# waveshare_v4.net
KiCad netlist of a schematic drawn in EAGLE
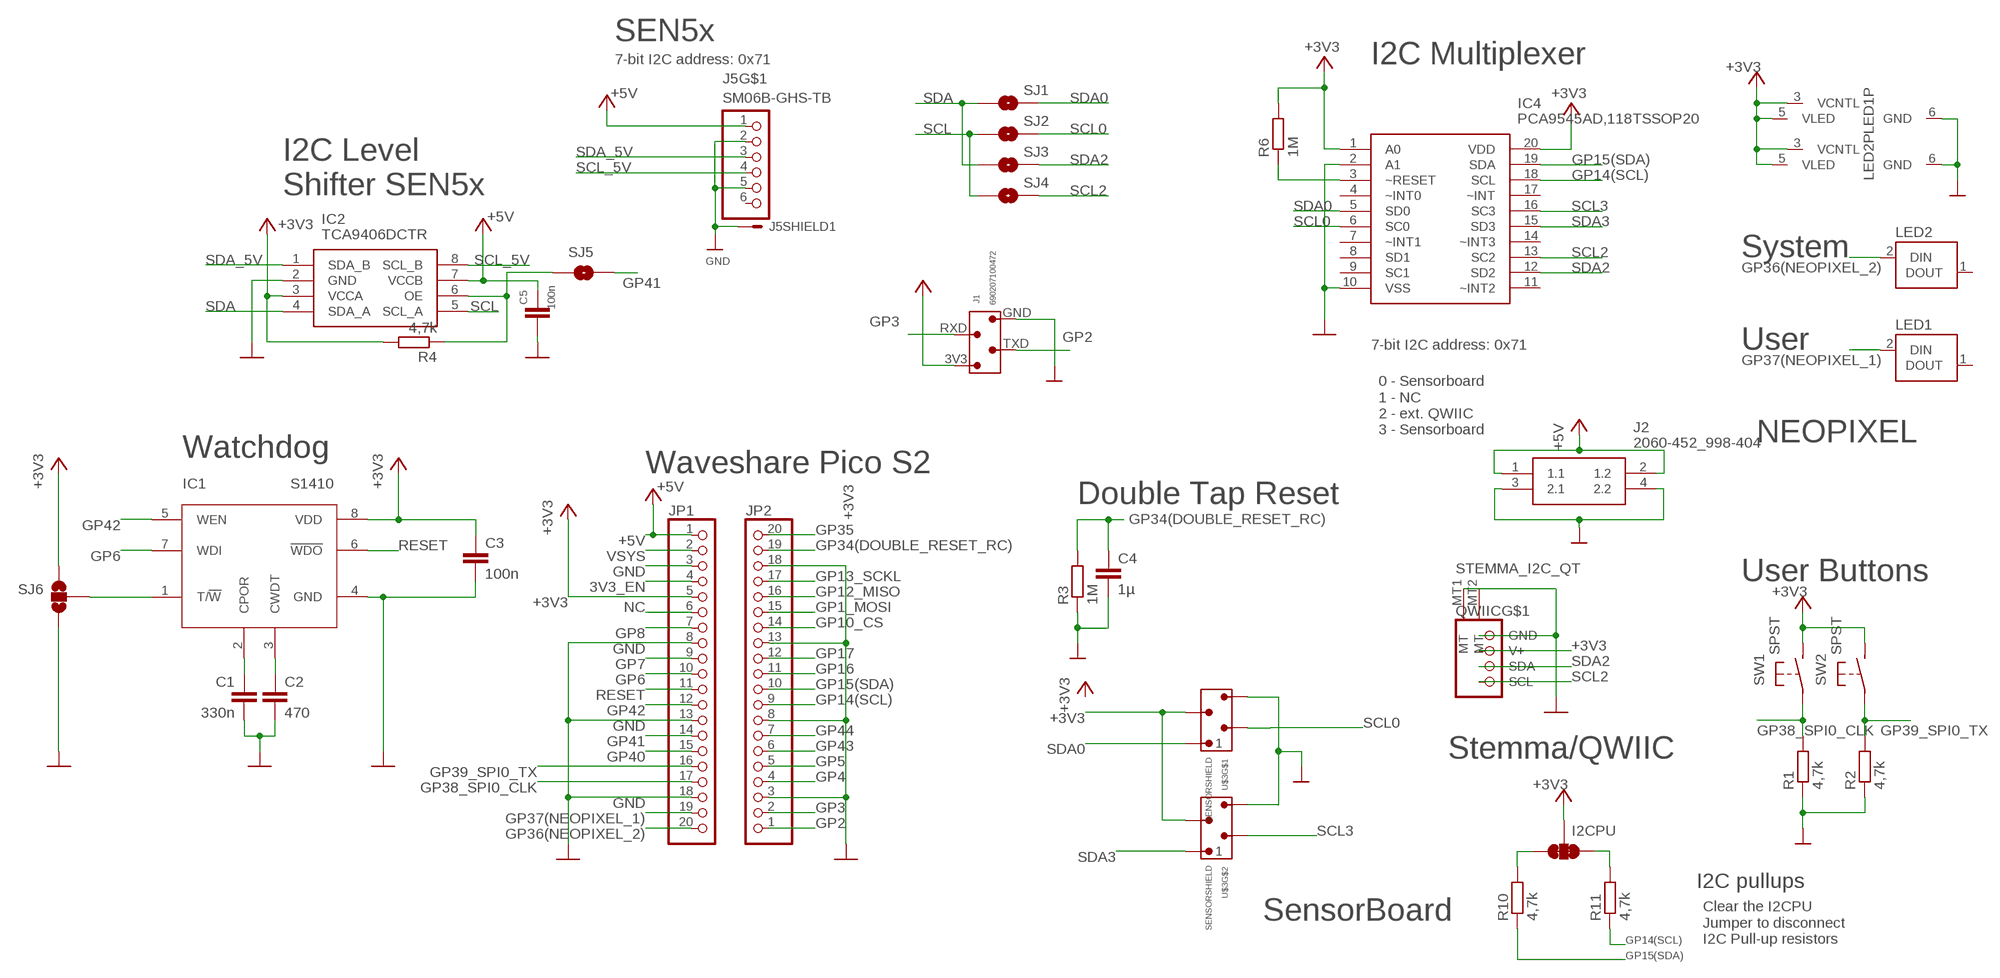
[diagram p0: schematic, sheet 1]

(export (version "E")
  (design (tool "Eeschema 10.0.6"))
  (components
    (comp (ref "C1")
      (value "330n")
      (footprint "eagle-import:C0603")
      (libsource (lib "eagle-import") (part "C-EUC0603"))
    )
    (comp (ref "C2")
      (value "470")
      (footprint "eagle-import:C0603")
      (libsource (lib "eagle-import") (part "C-EUC0603"))
    )
    (comp (ref "C3")
      (value "100n")
      (footprint "eagle-import:C0603")
      (libsource (lib "eagle-import") (part "C-EUC0603"))
    )
    (comp (ref "C4")
      (value "1µ")
      (footprint "eagle-import:C0603")
      (libsource (lib "eagle-import") (part "C-EUC0603"))
    )
    (comp (ref "C5")
      (value "100n")
      (footprint "eagle-import:C0603")
      (libsource (lib "eagle-import") (part "C-EUC0603"))
    )
    (comp (ref "I2CPU")
      (value "I2C PU")
      (footprint "eagle-import:SMT-JUMPER_3_2-NC_TRACE_SILK")
      (libsource (lib "eagle-import") (part "JUMPER-SMT_3_2-NC_TRACE_SILK"))
    )
    (comp (ref "IC1")
      (value "S1410")
      (footprint "eagle-import:MSOP08")
      (libsource (lib "eagle-import") (part "S1410"))
    )
    (comp (ref "IC2")
      (value "TCA9406DCTR")
      (footprint "eagle-import:SOP65P400X130-8N")
      (fields (field (name "MOUSER_PART_NUMBER") "595-TCA9406DCTR"))
      (libsource (lib "eagle-import") (part "TCA9406DCTR"))
    )
    (comp (ref "IC4")
      (value "PCA9545AD,118TSSOP20")
      (footprint "eagle-import:TSSOP20")
      (libsource (lib "eagle-import") (part "PCA9545AD,118TSSOP20"))
    )
    (comp (ref "J1")
      (value "690207100472")
      (footprint "eagle-import:LORASHIELD")
      (libsource (lib "eagle-import") (part "LORASHIELD"))
    )
    (comp (ref "J2")
      (value "2060-452_998-404")
      (footprint "eagle-import:2060452998404")
      (fields (field (name "ARROW_PART_NUMBER") "2060-452/998-404"))
      (libsource (lib "eagle-import") (part "2060-452_998-404"))
    )
    (comp (ref "J5")
      (value "SM06B-GHS-TB")
      (footprint "eagle-import:JST-PH-06-SMD")
      (libsource (lib "eagle-import") (part "JST-PH-06-SMDSMD"))
    )
    (comp (ref "JP1")
      (value "PINHD-1X20")
      (footprint "eagle-import:1X20")
      (libsource (lib "eagle-import") (part "PINHD-1X20"))
    )
    (comp (ref "JP2")
      (value "PINHD-1X20")
      (footprint "eagle-import:1X20")
      (libsource (lib "eagle-import") (part "PINHD-1X20"))
    )
    (comp (ref "LED1")
      (value "WS2812WS2812")
      (footprint "eagle-import:WS2812")
      (libsource (lib "eagle-import") (part "WS2812WS2812"))
    )
    (comp (ref "LED2")
      (value "WS2812WS2812")
      (footprint "eagle-import:WS2812")
      (libsource (lib "eagle-import") (part "WS2812WS2812"))
    )
    (comp (ref "QWIIC")
      (value "STEMMA_I2C_QT")
      (footprint "eagle-import:JST_SH4")
      (libsource (lib "eagle-import") (part "STEMMA_I2C_QT"))
    )
    (comp (ref "R1")
      (value "4,7k")
      (footprint "eagle-import:R0603")
      (libsource (lib "eagle-import") (part "R-EU_R0603"))
    )
    (comp (ref "R2")
      (value "4,7k")
      (footprint "eagle-import:R0603")
      (libsource (lib "eagle-import") (part "R-EU_R0603"))
    )
    (comp (ref "R3")
      (value "1M")
      (footprint "eagle-import:R0603")
      (libsource (lib "eagle-import") (part "R-EU_R0603"))
    )
    (comp (ref "R4")
      (value "4,7k")
      (footprint "eagle-import:R0603")
      (libsource (lib "eagle-import") (part "R-EU_R0603"))
    )
    (comp (ref "R6")
      (value "1M")
      (footprint "eagle-import:R0603")
      (libsource (lib "eagle-import") (part "R-EU_R0603"))
    )
    (comp (ref "R10")
      (value "4,7k")
      (footprint "eagle-import:R0603")
      (libsource (lib "eagle-import") (part "R-EU_R0603"))
    )
    (comp (ref "R11")
      (value "4,7k")
      (footprint "eagle-import:R0603")
      (libsource (lib "eagle-import") (part "R-EU_R0603"))
    )
    (comp (ref "SJ1")
      (value "SOLDERJUMPERNO")
      (footprint "eagle-import:SJ_2S-NO")
      (libsource (lib "eagle-import") (part "SOLDERJUMPERNO"))
    )
    (comp (ref "SJ2")
      (value "SOLDERJUMPERNO")
      (footprint "eagle-import:SJ_2S-NO")
      (libsource (lib "eagle-import") (part "SOLDERJUMPERNO"))
    )
    (comp (ref "SJ3")
      (value "SOLDERJUMPERNO")
      (footprint "eagle-import:SJ_2S-NO")
      (libsource (lib "eagle-import") (part "SOLDERJUMPERNO"))
    )
    (comp (ref "SJ4")
      (value "SOLDERJUMPERNO")
      (footprint "eagle-import:SJ_2S-NO")
      (libsource (lib "eagle-import") (part "SOLDERJUMPERNO"))
    )
    (comp (ref "SJ5")
      (value "SOLDERJUMPERNO")
      (footprint "eagle-import:SJ_2S-NO")
      (libsource (lib "eagle-import") (part "SOLDERJUMPERNO"))
    )
    (comp (ref "SJ6")
      (value "SOLDERJUMPER_2WAYTRACE1&2")
      (footprint "eagle-import:SJ_3_TRACE1&2")
      (libsource (lib "eagle-import") (part "SOLDERJUMPER_2WAYTRACE1&2"))
    )
    (comp (ref "SW1")
      (value "SPST")
      (footprint "eagle-import:DTSM-32S-B")
      (libsource (lib "eagle-import") (part "SPST"))
    )
    (comp (ref "SW2")
      (value "SPST")
      (footprint "eagle-import:DTSM-32S-B")
      (libsource (lib "eagle-import") (part "SPST"))
    )
    (comp (ref "U$3")
      (value "SENSORSHIELD")
      (footprint "eagle-import:SENSORSHIELD")
      (libsource (lib "eagle-import") (part "SENSORSHIELD"))
    )
  )
  (nets
    (net (code "1") (name "+3V3") (class "Default")
      (node (ref "C3") (pin "1") (pinfunction "1_1") (pintype "passive"))
      (node (ref "I2CPU") (pin "2") (pinfunction "2_2") (pintype "passive"))
      (node (ref "IC1") (pin "8") (pinfunction "VDD_8") (pintype "bidirectional"))
      (node (ref "IC2") (pin "3") (pinfunction "VCCA_3") (pintype "bidirectional"))
      (node (ref "IC4") (pin "1") (pinfunction "A0_1") (pintype "bidirectional"))
      (node (ref "IC4") (pin "20") (pinfunction "VDD_20") (pintype "bidirectional"))
      (node (ref "J1") (pin "3V3") (pinfunction "4_3V3") (pintype "passive"))
      (node (ref "JP1") (pin "5") (pinfunction "5_5") (pintype "passive"))
      (node (ref "LED1") (pin "3") (pinfunction "VCNTL_3") (pintype "power_in"))
      (node (ref "LED1") (pin "5") (pinfunction "VLED_5") (pintype "power_in"))
      (node (ref "LED2") (pin "3") (pinfunction "VCNTL_3") (pintype "power_in"))
      (node (ref "LED2") (pin "5") (pinfunction "VLED_5") (pintype "power_in"))
      (node (ref "QWIIC") (pin "2") (pinfunction "V+_2") (pintype "passive"))
      (node (ref "R4") (pin "2") (pinfunction "2_2") (pintype "passive"))
      (node (ref "R6") (pin "2") (pinfunction "2_2") (pintype "passive"))
      (node (ref "SJ6") (pin "1") (pinfunction "1_1") (pintype "passive"))
      (node (ref "SW1") (pin "P$2") (pinfunction "S_P$2") (pintype "passive"))
      (node (ref "SW2") (pin "P$2") (pinfunction "S_P$2") (pintype "passive"))
      (node (ref "U$3") (pin "3V3_1") (pinfunction "3_3V3_1") (pintype "passive"))
      (node (ref "U$3") (pin "3V3_2") (pinfunction "3_3V3_2") (pintype "passive"))
    )
    (net (code "2") (name "+5V") (class "Default")
      (node (ref "C5") (pin "1") (pinfunction "1_1") (pintype "passive"))
      (node (ref "IC2") (pin "7") (pinfunction "VCCB_7") (pintype "bidirectional"))
      (node (ref "J2") (pin "1") (pinfunction "1.1_1") (pintype "bidirectional"))
      (node (ref "J2") (pin "2") (pinfunction "1.2_2") (pintype "bidirectional"))
      (node (ref "J5") (pin "1") (pinfunction "1_1") (pintype "passive"))
      (node (ref "JP1") (pin "1") (pinfunction "1_1") (pintype "passive"))
    )
    (net (code "3") (name "/NC") (class "Default")
      (node (ref "JP1") (pin "6") (pinfunction "6_6") (pintype "passive"))
    )
    (net (code "4") (name "/SCL") (class "Default")
      (node (ref "IC2") (pin "5") (pinfunction "SCL_A_5") (pintype "bidirectional"))
      (node (ref "SJ2") (pin "1") (pinfunction "1_1") (pintype "passive"))
      (node (ref "SJ4") (pin "1") (pinfunction "1_1") (pintype "passive"))
    )
    (net (code "5") (name "/SCL_5V") (class "Default")
      (node (ref "IC2") (pin "8") (pinfunction "SCL_B_8") (pintype "bidirectional"))
      (node (ref "J5") (pin "4") (pinfunction "4_4") (pintype "passive"))
    )
    (net (code "6") (name "/SDA") (class "Default")
      (node (ref "IC2") (pin "4") (pinfunction "SDA_A_4") (pintype "bidirectional"))
      (node (ref "SJ1") (pin "1") (pinfunction "1_1") (pintype "passive"))
      (node (ref "SJ3") (pin "1") (pinfunction "1_1") (pintype "passive"))
    )
    (net (code "7") (name "/SDA_5V") (class "Default")
      (node (ref "IC2") (pin "1") (pinfunction "SDA_B_1") (pintype "bidirectional"))
      (node (ref "J5") (pin "3") (pinfunction "3_3") (pintype "passive"))
    )
    (net (code "8") (name "3V3_EN") (class "Default")
      (node (ref "JP1") (pin "4") (pinfunction "4_4") (pintype "passive"))
    )
    (net (code "9") (name "GND") (class "Default")
      (node (ref "C1") (pin "2") (pinfunction "2_2") (pintype "passive"))
      (node (ref "C2") (pin "2") (pinfunction "2_2") (pintype "passive"))
      (node (ref "C3") (pin "2") (pinfunction "2_2") (pintype "passive"))
      (node (ref "C4") (pin "2") (pinfunction "2_2") (pintype "passive"))
      (node (ref "C5") (pin "2") (pinfunction "2_2") (pintype "passive"))
      (node (ref "IC1") (pin "4") (pinfunction "GND_4") (pintype "bidirectional"))
      (node (ref "IC2") (pin "2") (pinfunction "GND_2") (pintype "bidirectional"))
      (node (ref "IC4") (pin "10") (pinfunction "VSS_10") (pintype "bidirectional"))
      (node (ref "IC4") (pin "2") (pinfunction "A1_2") (pintype "bidirectional"))
      (node (ref "J1") (pin "GND") (pinfunction "1_GND") (pintype "passive"))
      (node (ref "J2") (pin "3") (pinfunction "2.1_3") (pintype "bidirectional"))
      (node (ref "J2") (pin "4") (pinfunction "2.2_4") (pintype "bidirectional"))
      (node (ref "J5") (pin "2") (pinfunction "2_2") (pintype "passive"))
      (node (ref "J5") (pin "5") (pinfunction "5_5") (pintype "passive"))
      (node (ref "J5") (pin "7") (pinfunction "S_7") (pintype "passive"))
      (node (ref "J5") (pin "8") (pinfunction "S_8") (pintype "passive"))
      (node (ref "JP1") (pin "13") (pinfunction "13_13") (pintype "passive"))
      (node (ref "JP1") (pin "18") (pinfunction "18_18") (pintype "passive"))
      (node (ref "JP1") (pin "3") (pinfunction "3_3") (pintype "passive"))
      (node (ref "JP1") (pin "8") (pinfunction "8_8") (pintype "passive"))
      (node (ref "JP2") (pin "13") (pinfunction "13_13") (pintype "passive"))
      (node (ref "JP2") (pin "18") (pinfunction "18_18") (pintype "passive"))
      (node (ref "JP2") (pin "3") (pinfunction "3_3") (pintype "passive"))
      (node (ref "JP2") (pin "8") (pinfunction "8_8") (pintype "passive"))
      (node (ref "LED1") (pin "6") (pinfunction "GND_6") (pintype "power_in"))
      (node (ref "LED2") (pin "6") (pinfunction "GND_6") (pintype "power_in"))
      (node (ref "QWIIC") (pin "1") (pinfunction "GND_1") (pintype "passive"))
      (node (ref "QWIIC") (pin "MT1") (pinfunction "MT_MT1") (pintype "bidirectional"))
      (node (ref "QWIIC") (pin "MT2") (pinfunction "MT_MT2") (pintype "bidirectional"))
      (node (ref "R1") (pin "1") (pinfunction "1_1") (pintype "passive"))
      (node (ref "R2") (pin "1") (pinfunction "1_1") (pintype "passive"))
      (node (ref "R3") (pin "1") (pinfunction "1_1") (pintype "passive"))
      (node (ref "SJ6") (pin "3") (pinfunction "3_3") (pintype "passive"))
      (node (ref "U$3") (pin "GND_1") (pinfunction "4_GND_1") (pintype "passive"))
      (node (ref "U$3") (pin "GND_2") (pinfunction "4_GND_2") (pintype "passive"))
    )
    (net (code "10") (name "GP1_MOSI") (class "Default")
      (node (ref "JP2") (pin "15") (pinfunction "15_15") (pintype "passive"))
    )
    (net (code "11") (name "GP2") (class "Default")
      (node (ref "J1") (pin "TXD") (pinfunction "3_TXD") (pintype "passive"))
      (node (ref "JP2") (pin "1") (pinfunction "1_1") (pintype "passive"))
    )
    (net (code "12") (name "GP3") (class "Default")
      (node (ref "J1") (pin "RXD") (pinfunction "2_RXD") (pintype "passive"))
      (node (ref "JP2") (pin "2") (pinfunction "2_2") (pintype "passive"))
    )
    (net (code "13") (name "GP4") (class "Default")
      (node (ref "JP2") (pin "4") (pinfunction "4_4") (pintype "passive"))
    )
    (net (code "14") (name "GP5") (class "Default")
      (node (ref "JP2") (pin "5") (pinfunction "5_5") (pintype "passive"))
    )
    (net (code "15") (name "GP6") (class "Default")
      (node (ref "IC1") (pin "7") (pinfunction "WDI_7") (pintype "bidirectional"))
      (node (ref "JP1") (pin "10") (pinfunction "10_10") (pintype "passive"))
    )
    (net (code "16") (name "GP7") (class "Default")
      (node (ref "JP1") (pin "9") (pinfunction "9_9") (pintype "passive"))
    )
    (net (code "17") (name "GP8") (class "Default")
      (node (ref "JP1") (pin "7") (pinfunction "7_7") (pintype "passive"))
    )
    (net (code "18") (name "GP10_CS") (class "Default")
      (node (ref "JP2") (pin "14") (pinfunction "14_14") (pintype "passive"))
    )
    (net (code "19") (name "GP12_MISO") (class "Default")
      (node (ref "JP2") (pin "16") (pinfunction "16_16") (pintype "passive"))
    )
    (net (code "20") (name "GP13_SCKL") (class "Default")
      (node (ref "JP2") (pin "17") (pinfunction "17_17") (pintype "passive"))
    )
    (net (code "21") (name "GP14(SCL)") (class "Default")
      (node (ref "IC4") (pin "18") (pinfunction "SCL_18") (pintype "bidirectional"))
      (node (ref "JP2") (pin "9") (pinfunction "9_9") (pintype "passive"))
      (node (ref "R11") (pin "1") (pinfunction "1_1") (pintype "passive"))
    )
    (net (code "22") (name "GP15(SDA)") (class "Default")
      (node (ref "IC4") (pin "19") (pinfunction "SDA_19") (pintype "bidirectional"))
      (node (ref "JP2") (pin "10") (pinfunction "10_10") (pintype "passive"))
      (node (ref "R10") (pin "1") (pinfunction "1_1") (pintype "passive"))
    )
    (net (code "23") (name "GP16") (class "Default")
      (node (ref "JP2") (pin "11") (pinfunction "11_11") (pintype "passive"))
    )
    (net (code "24") (name "GP17") (class "Default")
      (node (ref "JP2") (pin "12") (pinfunction "12_12") (pintype "passive"))
    )
    (net (code "25") (name "GP34(DOUBLE_RESET_RC)") (class "Default")
      (node (ref "C4") (pin "1") (pinfunction "1_1") (pintype "passive"))
      (node (ref "JP2") (pin "19") (pinfunction "19_19") (pintype "passive"))
      (node (ref "R3") (pin "2") (pinfunction "2_2") (pintype "passive"))
    )
    (net (code "26") (name "GP35") (class "Default")
      (node (ref "JP2") (pin "20") (pinfunction "20_20") (pintype "passive"))
    )
    (net (code "27") (name "GP36(NEOPIXEL_2)") (class "Default")
      (node (ref "JP1") (pin "20") (pinfunction "20_20") (pintype "passive"))
      (node (ref "LED2") (pin "2") (pinfunction "DIN_2") (pintype "input"))
    )
    (net (code "28") (name "GP37(NEOPIXEL_1)") (class "Default")
      (node (ref "JP1") (pin "19") (pinfunction "19_19") (pintype "passive"))
      (node (ref "LED1") (pin "2") (pinfunction "DIN_2") (pintype "input"))
    )
    (net (code "29") (name "GP38_SPI0_CLK") (class "Default")
      (node (ref "JP1") (pin "17") (pinfunction "17_17") (pintype "passive"))
      (node (ref "R1") (pin "2") (pinfunction "2_2") (pintype "passive"))
      (node (ref "SW1") (pin "P$1") (pinfunction "P_P$1") (pintype "passive"))
    )
    (net (code "30") (name "GP39_SPI0_TX") (class "Default")
      (node (ref "JP1") (pin "16") (pinfunction "16_16") (pintype "passive"))
      (node (ref "R2") (pin "2") (pinfunction "2_2") (pintype "passive"))
      (node (ref "SW2") (pin "P$1") (pinfunction "P_P$1") (pintype "passive"))
    )
    (net (code "31") (name "GP40") (class "Default")
      (node (ref "JP1") (pin "15") (pinfunction "15_15") (pintype "passive"))
    )
    (net (code "32") (name "GP41") (class "Default")
      (node (ref "JP1") (pin "14") (pinfunction "14_14") (pintype "passive"))
      (node (ref "SJ5") (pin "2") (pinfunction "2_2") (pintype "passive"))
    )
    (net (code "33") (name "GP42") (class "Default")
      (node (ref "IC1") (pin "5") (pinfunction "WEN_5") (pintype "bidirectional"))
      (node (ref "JP1") (pin "12") (pinfunction "12_12") (pintype "passive"))
    )
    (net (code "34") (name "GP43") (class "Default")
      (node (ref "JP2") (pin "6") (pinfunction "6_6") (pintype "passive"))
    )
    (net (code "35") (name "GP44") (class "Default")
      (node (ref "JP2") (pin "7") (pinfunction "7_7") (pintype "passive"))
    )
    (net (code "36") (name "Net-(I2CPU-Pad1)") (class "Default")
      (node (ref "I2CPU") (pin "1") (pinfunction "1_1") (pintype "passive"))
      (node (ref "R11") (pin "2") (pinfunction "2_2") (pintype "passive"))
    )
    (net (code "37") (name "Net-(I2CPU-Pad3)") (class "Default")
      (node (ref "I2CPU") (pin "3") (pinfunction "3_3") (pintype "passive"))
      (node (ref "R10") (pin "2") (pinfunction "2_2") (pintype "passive"))
    )
    (net (code "38") (name "Net-(IC1-CPOR)") (class "Default")
      (node (ref "C1") (pin "1") (pinfunction "1_1") (pintype "passive"))
      (node (ref "IC1") (pin "2") (pinfunction "CPOR_2") (pintype "bidirectional"))
    )
    (net (code "39") (name "Net-(IC1-CWDT)") (class "Default")
      (node (ref "C2") (pin "1") (pinfunction "1_1") (pintype "passive"))
      (node (ref "IC1") (pin "3") (pinfunction "CWDT_3") (pintype "bidirectional"))
    )
    (net (code "40") (name "Net-(IC1-T{slash}~{W})") (class "Default")
      (node (ref "IC1") (pin "1") (pinfunction "T/~{W}_1") (pintype "bidirectional"))
      (node (ref "SJ6") (pin "2") (pinfunction "2_2") (pintype "passive"))
    )
    (net (code "41") (name "Net-(IC2-OE)") (class "Default")
      (node (ref "IC2") (pin "6") (pinfunction "OE_6") (pintype "bidirectional"))
      (node (ref "R4") (pin "1") (pinfunction "1_1") (pintype "passive"))
      (node (ref "SJ5") (pin "1") (pinfunction "1_1") (pintype "passive"))
    )
    (net (code "42") (name "Net-(IC4-~{RESET})") (class "Default")
      (node (ref "IC4") (pin "3") (pinfunction "~{RESET}_3") (pintype "bidirectional"))
      (node (ref "R6") (pin "1") (pinfunction "1_1") (pintype "passive"))
    )
    (net (code "43") (name "RESET") (class "Default")
      (node (ref "IC1") (pin "6") (pinfunction "~{WDO}_6") (pintype "bidirectional"))
      (node (ref "JP1") (pin "11") (pinfunction "11_11") (pintype "passive"))
    )
    (net (code "44") (name "SCL0") (class "Default")
      (node (ref "IC4") (pin "6") (pinfunction "SC0_6") (pintype "bidirectional"))
      (node (ref "SJ2") (pin "2") (pinfunction "2_2") (pintype "passive"))
      (node (ref "U$3") (pin "SCL0") (pinfunction "2_SCL0") (pintype "passive"))
    )
    (net (code "45") (name "SCL2") (class "Default")
      (node (ref "IC4") (pin "13") (pinfunction "SC2_13") (pintype "bidirectional"))
      (node (ref "QWIIC") (pin "4") (pinfunction "SCL_4") (pintype "passive"))
      (node (ref "SJ4") (pin "2") (pinfunction "2_2") (pintype "passive"))
    )
    (net (code "46") (name "SCL3") (class "Default")
      (node (ref "IC4") (pin "16") (pinfunction "SC3_16") (pintype "bidirectional"))
      (node (ref "U$3") (pin "SCL1") (pinfunction "2_SCL1") (pintype "passive"))
    )
    (net (code "47") (name "SDA0") (class "Default")
      (node (ref "IC4") (pin "5") (pinfunction "SD0_5") (pintype "bidirectional"))
      (node (ref "SJ1") (pin "2") (pinfunction "2_2") (pintype "passive"))
      (node (ref "U$3") (pin "SDA0") (pinfunction "1_SDA0") (pintype "passive"))
    )
    (net (code "48") (name "SDA2") (class "Default")
      (node (ref "IC4") (pin "12") (pinfunction "SD2_12") (pintype "bidirectional"))
      (node (ref "QWIIC") (pin "3") (pinfunction "SDA_3") (pintype "passive"))
      (node (ref "SJ3") (pin "2") (pinfunction "2_2") (pintype "passive"))
    )
    (net (code "49") (name "SDA3") (class "Default")
      (node (ref "IC4") (pin "15") (pinfunction "SD3_15") (pintype "bidirectional"))
      (node (ref "U$3") (pin "SDA1") (pinfunction "1_SDA1") (pintype "passive"))
    )
    (net (code "50") (name "VSYS") (class "Default")
      (node (ref "JP1") (pin "2") (pinfunction "2_2") (pintype "passive"))
    )
    (net (code "51") (name "unconnected-(IC4-SC1-Pad9)") (class "Default")
      (node (ref "IC4") (pin "9") (pinfunction "SC1_9") (pintype "bidirectional"))
    )
    (net (code "52") (name "unconnected-(IC4-SD1-Pad8)") (class "Default")
      (node (ref "IC4") (pin "8") (pinfunction "SD1_8") (pintype "bidirectional"))
    )
    (net (code "53") (name "unconnected-(IC4-~{INT0}-Pad4)") (class "Default")
      (node (ref "IC4") (pin "4") (pinfunction "~{INT0}_4") (pintype "bidirectional"))
    )
    (net (code "54") (name "unconnected-(IC4-~{INT1}-Pad7)") (class "Default")
      (node (ref "IC4") (pin "7") (pinfunction "~{INT1}_7") (pintype "bidirectional"))
    )
    (net (code "55") (name "unconnected-(IC4-~{INT2}-Pad11)") (class "Default")
      (node (ref "IC4") (pin "11") (pinfunction "~{INT2}_11") (pintype "bidirectional"))
    )
    (net (code "56") (name "unconnected-(IC4-~{INT3}-Pad14)") (class "Default")
      (node (ref "IC4") (pin "14") (pinfunction "~{INT3}_14") (pintype "bidirectional"))
    )
    (net (code "57") (name "unconnected-(IC4-~{INT}-Pad17)") (class "Default")
      (node (ref "IC4") (pin "17") (pinfunction "~{INT}_17") (pintype "bidirectional"))
    )
    (net (code "58") (name "unconnected-(J5-Pad6)") (class "Default")
      (node (ref "J5") (pin "6") (pinfunction "6_6") (pintype "passive"))
    )
    (net (code "59") (name "unconnected-(LED1B-DOUT-Pad1)") (class "Default")
      (node (ref "LED1") (pin "1") (pinfunction "DOUT_1") (pintype "output"))
    )
    (net (code "60") (name "unconnected-(LED2B-DOUT-Pad1)") (class "Default")
      (node (ref "LED2") (pin "1") (pinfunction "DOUT_1") (pintype "output"))
    )
  )
)
